# tx.net
KiCad netlist of a schematic drawn in EAGLE
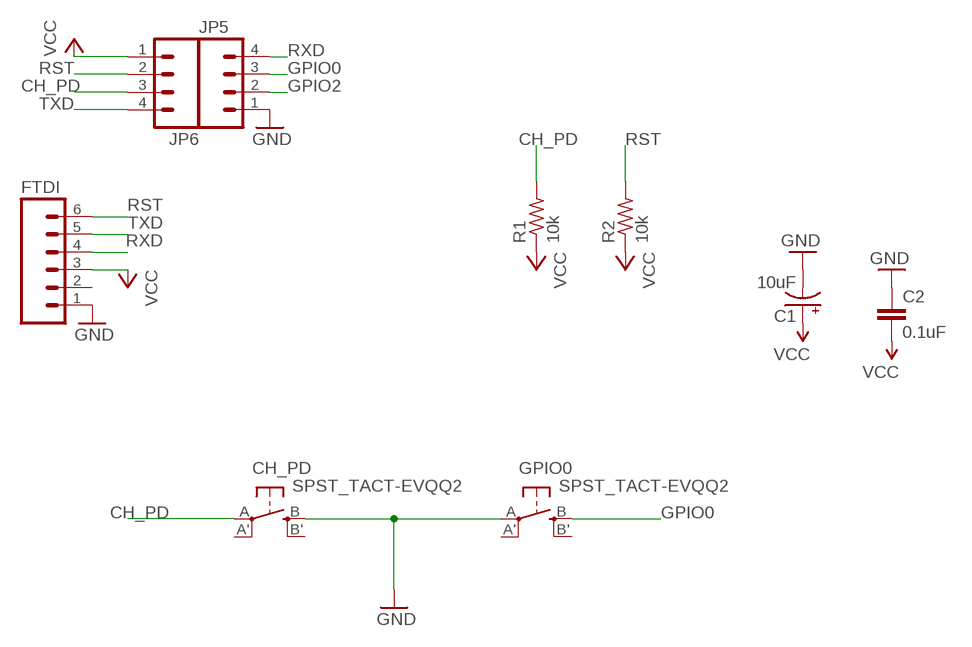
[diagram p0: schematic, sheet 1]

(export (version "E")
  (design (tool "Eeschema 10.0.6"))
  (components
    (comp (ref "C1")
      (value "10uF")
      (footprint "eagle-import:EIA6032")
      (libsource (lib "eagle-import") (part "CAP_POL6032"))
    )
    (comp (ref "C2")
      (value "0.1uF")
      (footprint "eagle-import:0603-CAP")
      (libsource (lib "eagle-import") (part "0.1UF-100V-10%(0603)"))
    )
    (comp (ref "CH_PD")
      (value "SPST_TACT-EVQQ2")
      (footprint "eagle-import:EVQ-Q2")
      (libsource (lib "eagle-import") (part "SPST_TACT-EVQQ2"))
    )
    (comp (ref "FTDI")
      (value "M06SILK_FEMALE_PTH")
      (footprint "eagle-import:1X06")
      (libsource (lib "eagle-import") (part "M06SILK_FEMALE_PTH"))
    )
    (comp (ref "GPIO0")
      (value "SPST_TACT-EVQQ2")
      (footprint "eagle-import:EVQ-Q2")
      (libsource (lib "eagle-import") (part "SPST_TACT-EVQQ2"))
    )
    (comp (ref "JP5")
      (value "M041X04_NO_SILK")
      (footprint "eagle-import:1X04_NO_SILK")
      (libsource (lib "eagle-import") (part "M041X04_NO_SILK"))
    )
    (comp (ref "JP6")
      (value "M041X04_NO_SILK")
      (footprint "eagle-import:1X04_NO_SILK")
      (libsource (lib "eagle-import") (part "M041X04_NO_SILK"))
    )
    (comp (ref "R1")
      (value "10k")
      (footprint "eagle-import:R0805")
      (libsource (lib "eagle-import") (part "R-US_R0805"))
    )
    (comp (ref "R2")
      (value "10k")
      (footprint "eagle-import:R0805")
      (libsource (lib "eagle-import") (part "R-US_R0805"))
    )
  )
  (nets
    (net (code "1") (name "/CH_PD") (class "Default")
      (node (ref "CH_PD") (pin "A") (pinfunction "P_A") (pintype "passive"))
      (node (ref "JP6") (pin "3") (pinfunction "3_3") (pintype "passive"))
      (node (ref "R1") (pin "2") (pinfunction "2_2") (pintype "passive"))
    )
    (net (code "2") (name "/GPIO0") (class "Default")
      (node (ref "GPIO0") (pin "B") (pinfunction "S_B") (pintype "passive"))
      (node (ref "JP5") (pin "3") (pinfunction "3_3") (pintype "passive"))
    )
    (net (code "3") (name "/GPIO2") (class "Default")
      (node (ref "JP5") (pin "2") (pinfunction "2_2") (pintype "passive"))
    )
    (net (code "4") (name "/RST") (class "Default")
      (node (ref "FTDI") (pin "6") (pinfunction "6_6") (pintype "passive"))
      (node (ref "JP6") (pin "2") (pinfunction "2_2") (pintype "passive"))
      (node (ref "R2") (pin "2") (pinfunction "2_2") (pintype "passive"))
    )
    (net (code "5") (name "/RXD") (class "Default")
      (node (ref "FTDI") (pin "4") (pinfunction "4_4") (pintype "passive"))
      (node (ref "JP5") (pin "4") (pinfunction "4_4") (pintype "passive"))
    )
    (net (code "6") (name "/TXD") (class "Default")
      (node (ref "FTDI") (pin "5") (pinfunction "5_5") (pintype "passive"))
      (node (ref "JP6") (pin "4") (pinfunction "4_4") (pintype "passive"))
    )
    (net (code "7") (name "GND") (class "Default")
      (node (ref "C1") (pin "P$2") (pinfunction "-_P$2") (pintype "passive"))
      (node (ref "C2") (pin "1") (pinfunction "1_1") (pintype "passive"))
      (node (ref "CH_PD") (pin "B") (pinfunction "S_B") (pintype "passive"))
      (node (ref "FTDI") (pin "1") (pinfunction "1_1") (pintype "passive"))
      (node (ref "GPIO0") (pin "A") (pinfunction "P_A") (pintype "passive"))
      (node (ref "JP5") (pin "1") (pinfunction "1_1") (pintype "passive"))
    )
    (net (code "8") (name "VCC") (class "Default")
      (node (ref "C1") (pin "P$1") (pinfunction "+_P$1") (pintype "passive"))
      (node (ref "C2") (pin "2") (pinfunction "2_2") (pintype "passive"))
      (node (ref "FTDI") (pin "3") (pinfunction "3_3") (pintype "passive"))
      (node (ref "JP6") (pin "1") (pinfunction "1_1") (pintype "passive"))
      (node (ref "R1") (pin "1") (pinfunction "1_1") (pintype "passive"))
      (node (ref "R2") (pin "1") (pinfunction "1_1") (pintype "passive"))
    )
    (net (code "9") (name "unconnected-(CH_PD-P1-PadA')") (class "Default")
      (node (ref "CH_PD") (pin "A'") (pinfunction "P1_A'") (pintype "passive"))
    )
    (net (code "10") (name "unconnected-(CH_PD-S1-PadB')") (class "Default")
      (node (ref "CH_PD") (pin "B'") (pinfunction "S1_B'") (pintype "passive"))
    )
    (net (code "11") (name "unconnected-(FTDI-Pad2)") (class "Default")
      (node (ref "FTDI") (pin "2") (pinfunction "2_2") (pintype "passive"))
    )
    (net (code "12") (name "unconnected-(GPIO0-P1-PadA')") (class "Default")
      (node (ref "GPIO0") (pin "A'") (pinfunction "P1_A'") (pintype "passive"))
    )
    (net (code "13") (name "unconnected-(GPIO0-S1-PadB')") (class "Default")
      (node (ref "GPIO0") (pin "B'") (pinfunction "S1_B'") (pintype "passive"))
    )
  )
)
